# Hall_sensor_V1_power.net
KiCad netlist of a schematic drawn in Altium Designer
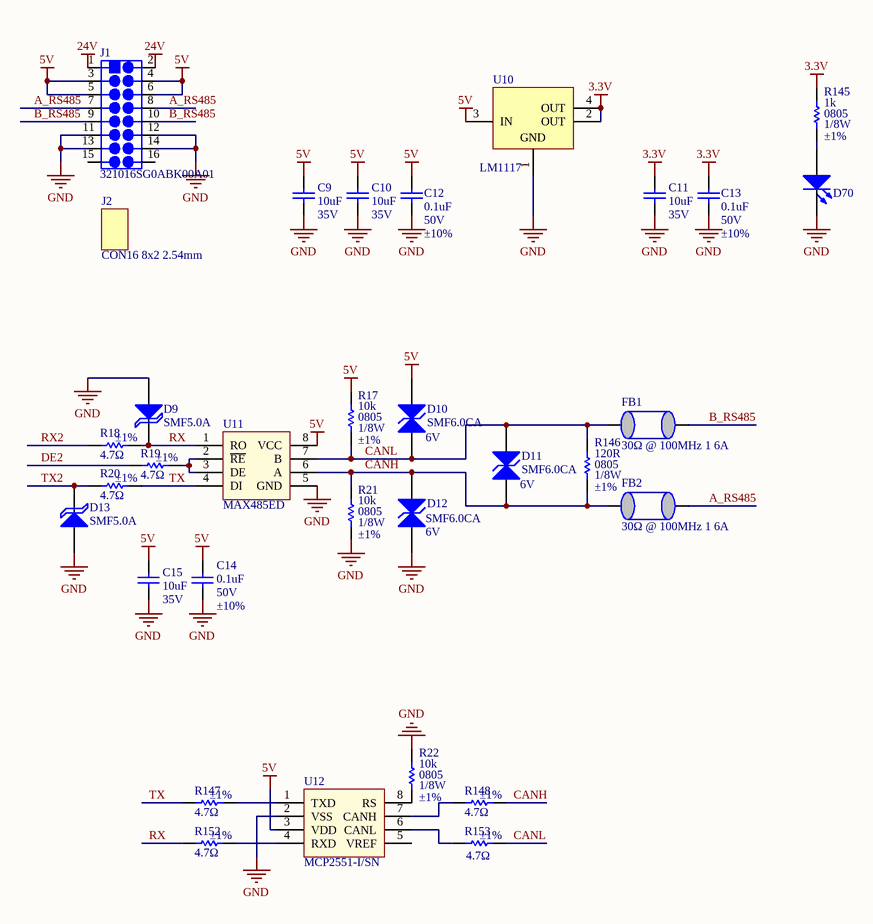
[diagram p0: Hall sensor V1 power.SchDoc]

(export (version "E")
  (design (tool "Eeschema 10.0.6"))
  (components
    (comp (ref "C9")
      (value "10uF")
      (footprint "CAP_SMD_0805")
      (description "10uF ±10% 35V X5R 0805 Multilayer Ceramic Capacitors MLCC - SMD/SMT RoHS")
      (fields
        (field (name "MANUFACTURER1_PART#") "GRM21BR6YA106KE43L")
        (field (name "MANUFACTURER2_PART#") "C2012X5R1V106MT000E")
        (field (name "VOLTAGE") "35V")
        (field (name "BY") "Thanh Son")
      )
      (libsource (lib "Full") (part "Cap-NP-100"))
    )
    (comp (ref "C10")
      (value "10uF")
      (footprint "CAP_SMD_0805")
      (description "10uF ±10% 35V X5R 0805 Multilayer Ceramic Capacitors MLCC - SMD/SMT RoHS")
      (fields
        (field (name "MANUFACTURER1_PART#") "GRM21BR6YA106KE43L")
        (field (name "MANUFACTURER2_PART#") "C2012X5R1V106MT000E")
        (field (name "VOLTAGE") "35V")
        (field (name "BY") "Thanh Son")
      )
      (libsource (lib "Full") (part "Cap-NP-100"))
    )
    (comp (ref "C11")
      (value "10uF")
      (footprint "CAP_SMD_0805")
      (description "10uF ±10% 35V X5R 0805 Multilayer Ceramic Capacitors MLCC - SMD/SMT RoHS")
      (fields
        (field (name "MANUFACTURER1_PART#") "GRM21BR6YA106KE43L")
        (field (name "MANUFACTURER2_PART#") "C2012X5R1V106MT000E")
        (field (name "VOLTAGE") "35V")
        (field (name "BY") "Thanh Son")
      )
      (libsource (lib "Full") (part "Cap-NP-100"))
    )
    (comp (ref "C12")
      (value "0.1uF")
      (footprint "CAP_SMD_0805")
      (description "100nF ±10% 50V X7R 0805 Multilayer Ceramic Capacitors MLCC - SMD/SMT RoHS")
      (fields
        (field (name "MANUFACTURER1_PART#") "C0805B104K500NT")
        (field (name "MANUFACTURER2_PART#") "TCC0805X7R104K500DT")
        (field (name "VOLTAGE") "50V")
        (field (name "TOLERANCE") "±10%")
        (field (name "BY") "Thanh Son")
      )
      (libsource (lib "Full") (part "Cap-NP-100"))
    )
    (comp (ref "C13")
      (value "0.1uF")
      (footprint "CAP_SMD_0805")
      (description "100nF ±10% 50V X7R 0805 Multilayer Ceramic Capacitors MLCC - SMD/SMT RoHS")
      (fields
        (field (name "MANUFACTURER1_PART#") "C0805B104K500NT")
        (field (name "MANUFACTURER2_PART#") "TCC0805X7R104K500DT")
        (field (name "VOLTAGE") "50V")
        (field (name "TOLERANCE") "±10%")
        (field (name "BY") "Thanh Son")
      )
      (libsource (lib "Full") (part "Cap-NP-100"))
    )
    (comp (ref "C14")
      (value "0.1uF")
      (footprint "CAP_SMD_0805")
      (description "100nF ±10% 50V X7R 0805 Multilayer Ceramic Capacitors MLCC - SMD/SMT RoHS")
      (fields
        (field (name "MANUFACTURER1_PART#") "C0805B104K500NT")
        (field (name "MANUFACTURER2_PART#") "TCC0805X7R104K500DT")
        (field (name "VOLTAGE") "50V")
        (field (name "TOLERANCE") "±10%")
        (field (name "BY") "Thanh Son")
      )
      (libsource (lib "Full") (part "Cap-NP-100"))
    )
    (comp (ref "C15")
      (value "10uF")
      (footprint "CAP_SMD_0805")
      (description "10uF ±10% 35V X5R 0805 Multilayer Ceramic Capacitors MLCC - SMD/SMT RoHS")
      (fields
        (field (name "MANUFACTURER1_PART#") "GRM21BR6YA106KE43L")
        (field (name "MANUFACTURER2_PART#") "C2012X5R1V106MT000E")
        (field (name "VOLTAGE") "35V")
        (field (name "BY") "Thanh Son")
      )
      (libsource (lib "Full") (part "Cap-NP-100"))
    )
    (comp (ref "D9")
      (value "SMF5.0A")
      (footprint "SOD-123")
      (description "SOD-123FL TVS RoHS")
      (fields (field (name "MANUFACTURER1_PART#") "SMF5.0A") (field (name "BY") "Thanh Son"))
      (libsource (lib "Full") (part "TVS SMF26A"))
    )
    (comp (ref "D10")
      (value "SMF6.0CA")
      (footprint "SOD-123")
      (description "Bidirectional 6V 6.67V 10.3V 19.4mA SOD-123FL TVS RoHS")
      (fields (field (name "VOLTAGE") "6V") (field (name "BY") "Thanh Son"))
      (libsource (lib "Full") (part "TVS SMF05CA  SOD123"))
    )
    (comp (ref "D11")
      (value "SMF6.0CA")
      (footprint "SOD-123")
      (description "Bidirectional 6V 6.67V 10.3V 19.4mA SOD-123FL TVS RoHS")
      (fields (field (name "VOLTAGE") "6V") (field (name "BY") "Thanh Son"))
      (libsource (lib "Full") (part "TVS SMF05CA  SOD123"))
    )
    (comp (ref "D12")
      (value "SMF6.0CA")
      (footprint "SOD-123")
      (description "Bidirectional 6V 6.67V 10.3V 19.4mA SOD-123FL TVS RoHS")
      (fields
        (field (name "MANUFACTURER1_PART#") "SMF6.0CA")
        (field (name "VOLTAGE") "6V")
        (field (name "BY") "Thanh Son")
      )
      (libsource (lib "Full") (part "TVS SMF05CA  SOD123"))
    )
    (comp (ref "D13")
      (value "SMF5.0A")
      (footprint "SOD-123")
      (description "SOD-123FL TVS RoHS")
      (fields (field (name "MANUFACTURER1_PART#") "SMF5.0A") (field (name "BY") "Thanh Son"))
      (libsource (lib "Full") (part "TVS SMF26A"))
    )
    (comp (ref "D70")
      (value "17-21/R6C-AQ2R2B/3T")
      (footprint "LED_SMD0805")
      (description "Red 617.5~633.5nm 0805 Light Emitting Diodes (LED) ROHS")
      (fields (field (name "MANUFACTURER2_PART#") "HSMH-C170"))
      (libsource (lib "Full") (part "LED_RED_SMD_0805"))
    )
    (comp (ref "FB1")
      (value "30Ω @ 100MHz 1 6A")
      (footprint "Inductor 0805")
      (description "30Ω @ 100MHz 1 6A 10mΩ 0805 Ferrite Beads ROHS")
      (fields
        (field (name "MANUFACTURER1_PART#") "CBM201209U300T")
        (field (name "MANUFACTURER2_PART#") "HCB2012KF-300T60")
        (field (name "BY") "Thanh Son")
      )
      (libsource (lib "Full") (part "inductor ferrite bead"))
    )
    (comp (ref "FB2")
      (value "30Ω @ 100MHz 1 6A")
      (footprint "Inductor 0805")
      (description "30Ω @ 100MHz 1 6A 10mΩ 0805 Ferrite Beads ROHS")
      (fields
        (field (name "MANUFACTURER1_PART#") "CBM201209U300T")
        (field (name "MANUFACTURER2_PART#") "HCB2012KF-300T60")
        (field (name "BY") "Thanh Son")
      )
      (libsource (lib "Full") (part "inductor ferrite bead"))
    )
    (comp (ref "J1")
      (value "header16 8x2 2.54mm")
      (footprint "Header IDC 8x2 2.54mm through hold")
      (description "16 2 0.100\"(2.54mm) Header Through Hole,P=2.54mm IDC Connectors ROHS")
      (fields
        (field (name "MANUFACTURER2_PART#") "B-3000S16P-0110")
        (field (name "MANUFACTURER1_PART#") "321016SG0ABK00A01")
        (field (name "BY") "Thanh Son")
      )
      (libsource (lib "Full") (part "header 8x2 JILN"))
    )
    (comp (ref "J2")
      (value "CON16 8x2 2.54mm")
      (description "16 2 0.100\"(2.54mm) - IDCconnector P=2.54mm IDC Connectors ROHS")
      (fields
        (field (name "MANUFACTURER1_PART#") "531416YBS0BW01")
        (field (name "MANUFACTURER2_PART#") "I-1010316P-B000")
        (field (name "BY") "Thanh Son")
      )
      (libsource (lib "Full") (part "CON 2 WJ2EDGR-5.08-2P"))
    )
    (comp (ref "R17")
      (value "10k")
      (footprint "RES_SMD_0805")
      (description "10kΩ ±1% 1/8W ±100ppm/℃ 0805 Chip Resistor - Surface Mount RoHS")
      (fields
        (field (name "MANUFACTURER1_PART#") "0805W8F1002T5E")
        (field (name "MANUFACTURER2_PART#") "RS-05K1002FT")
        (field (name "PCB FOOTPRINT") "0805")
        (field (name "POWER") "1/8W")
        (field (name "TOLERANCE") "±1%")
        (field (name "BY") "Thanh Son")
      )
      (libsource (lib "Full") (part "Res0.3"))
    )
    (comp (ref "R18")
      (value "4.7Ω")
      (footprint "RES_SMD_0805")
      (description "4.7Ω ±1% ±400ppm/℃ 0.125W 0805 Chip Resistor - Surface Mount ROHS")
      (fields
        (field (name "MANUFACTURER1_PART#") "0805W8F470KT5E")
        (field (name "MANUFACTURER2_PART#") "RC0805FR-074R7L")
        (field (name "TOLERANCE") "±1%")
      )
      (libsource (lib "Full") (part "Res0.3"))
    )
    (comp (ref "R19")
      (value "4.7Ω")
      (footprint "RES_SMD_0805")
      (description "4.7Ω ±1% ±400ppm/℃ 0.125W 0805 Chip Resistor - Surface Mount ROHS")
      (fields
        (field (name "MANUFACTURER1_PART#") "0805W8F470KT5E")
        (field (name "MANUFACTURER2_PART#") "RC0805FR-074R7L")
        (field (name "TOLERANCE") "±1%")
      )
      (libsource (lib "Full") (part "Res0.3"))
    )
    (comp (ref "R20")
      (value "4.7Ω")
      (footprint "RES_SMD_0805")
      (description "4.7Ω ±1% ±400ppm/℃ 0.125W 0805 Chip Resistor - Surface Mount ROHS")
      (fields
        (field (name "MANUFACTURER1_PART#") "0805W8F470KT5E")
        (field (name "MANUFACTURER2_PART#") "RC0805FR-074R7L")
        (field (name "TOLERANCE") "±1%")
      )
      (libsource (lib "Full") (part "Res0.3"))
    )
    (comp (ref "R21")
      (value "10k")
      (footprint "RES_SMD_0805")
      (description "10kΩ ±1% 1/8W ±100ppm/℃ 0805 Chip Resistor - Surface Mount RoHS")
      (fields
        (field (name "MANUFACTURER1_PART#") "0805W8F1002T5E")
        (field (name "MANUFACTURER2_PART#") "RS-05K1002FT")
        (field (name "PCB FOOTPRINT") "0805")
        (field (name "POWER") "1/8W")
        (field (name "TOLERANCE") "±1%")
        (field (name "BY") "Thanh Son")
      )
      (libsource (lib "Full") (part "Res0.3"))
    )
    (comp (ref "R22")
      (value "10k")
      (footprint "RES_SMD_0805")
      (description "10kΩ ±1% 1/8W ±100ppm/℃ 0805 Chip Resistor - Surface Mount RoHS")
      (fields
        (field (name "MANUFACTURER1_PART#") "0805W8F1002T5E")
        (field (name "MANUFACTURER2_PART#") "RS-05K1002FT")
        (field (name "PCB FOOTPRINT") "0805")
        (field (name "POWER") "1/8W")
        (field (name "TOLERANCE") "±1%")
        (field (name "BY") "Thanh Son")
      )
      (libsource (lib "Full") (part "Res0.3"))
    )
    (comp (ref "R145")
      (value "1k")
      (footprint "RES_SMD_0805")
      (description "10kΩ ±1% 1/8W ±100ppm/℃ 0805 Chip Resistor - Surface Mount RoHS")
      (fields
        (field (name "MANUFACTURER1_PART#") "AC0805FR-071KL")
        (field (name "MANUFACTURER2_PART#") "WR08X1001FTL")
        (field (name "PCB FOOTPRINT") "0805")
        (field (name "POWER") "1/8W")
        (field (name "TOLERANCE") "±1%")
        (field (name "BY") "Thanh Son")
      )
      (libsource (lib "Full") (part "Res0.3"))
    )
    (comp (ref "R146")
      (value "120R")
      (footprint "RES_SMD_0805")
      (description "±1% ±100ppm/℃ 120Ω 0.125W 0805 Chip Resistor - Surface Mount ROHS")
      (fields
        (field (name "MANUFACTURER1_PART#") "0805W8F1200T5E")
        (field (name "MANUFACTURER2_PART#") "AC0805FR-7W120RL")
        (field (name "PCB FOOTPRINT") "0805")
        (field (name "POWER") "1/8W")
        (field (name "TOLERANCE") "±1%")
        (field (name "BY") "Thanh Son")
      )
      (libsource (lib "Full") (part "Res0.3"))
    )
    (comp (ref "R147")
      (value "4.7Ω")
      (footprint "RES_SMD_0805")
      (description "4.7Ω ±1% ±400ppm/℃ 0.125W 0805 Chip Resistor - Surface Mount ROHS")
      (fields
        (field (name "MANUFACTURER1_PART#") "0805W8F470KT5E")
        (field (name "MANUFACTURER2_PART#") "RC0805FR-074R7L")
        (field (name "TOLERANCE") "±1%")
      )
      (libsource (lib "Full") (part "Res0.3"))
    )
    (comp (ref "R148")
      (value "4.7Ω")
      (footprint "RES_SMD_0805")
      (description "4.7Ω ±1% ±400ppm/℃ 0.125W 0805 Chip Resistor - Surface Mount ROHS")
      (fields
        (field (name "MANUFACTURER1_PART#") "0805W8F470KT5E")
        (field (name "MANUFACTURER2_PART#") "RC0805FR-074R7L")
        (field (name "TOLERANCE") "±1%")
      )
      (libsource (lib "Full") (part "Res0.3"))
    )
    (comp (ref "R152")
      (value "4.7Ω")
      (footprint "RES_SMD_0805")
      (description "4.7Ω ±1% ±400ppm/℃ 0.125W 0805 Chip Resistor - Surface Mount ROHS")
      (fields
        (field (name "MANUFACTURER1_PART#") "0805W8F470KT5E")
        (field (name "MANUFACTURER2_PART#") "RC0805FR-074R7L")
        (field (name "TOLERANCE") "±1%")
      )
      (libsource (lib "Full") (part "Res0.3"))
    )
    (comp (ref "R153")
      (value "4.7Ω")
      (footprint "RES_SMD_0805")
      (description "4.7Ω ±1% ±400ppm/℃ 0.125W 0805 Chip Resistor - Surface Mount ROHS")
      (fields
        (field (name "MANUFACTURER1_PART#") "0805W8F470KT5E")
        (field (name "MANUFACTURER2_PART#") "RC0805FR-074R7L")
        (field (name "TOLERANCE") "±1%")
      )
      (libsource (lib "Full") (part "Res0.3"))
    )
    (comp (ref "U10")
      (value "LM1117")
      (footprint "SOT223")
      (description "Fixed 18V 3.3V 1.4V @ 1A SOT-223 Dropout Regulators(LDO) RoHS")
      (fields
        (field (name "MANUFACTURER1_PART#") "AMS1117-3.3")
        (field (name "VOLTAGE") "3.3V")
        (field (name "BY") "Thanh Son")
      )
      (libsource (lib "Full") (part "LM1117"))
    )
    (comp (ref "U11")
      (value "MAX485ED")
      (footprint "SOIC8")
      (description "Transceiver RS485 1/1 200kbps SOIC-8_150mil RS-485/RS-422 ICs RoHS")
      (fields (field (name "MANUFACTURER2_PART#") "CBM485AS8") (field (name "BY") "Thanh Son"))
      (libsource (lib "Full") (part "RS 485 SIT3485ESA"))
    )
    (comp (ref "U12")
      (value "MCP2551-I/SN")
      (footprint "SOIC8")
      (description "Transceiver 1/1 CAN - SOIC-8_150mil CAN ICs ROHS")
      (fields (field (name "MANUFACTURER2_PART#") "PCA82C250T/YM,118") (field (name "BY") "Thanh Son"))
      (libsource (lib "Full") (part "CAN MCP2551-I/SN"))
    )
  )
  (nets
    (net (code "1") (name "/A_RS485") (class "Default")
      (node (ref "FB2") (pin "2") (pinfunction "2_2") (pintype "passive"))
      (node (ref "J1") (pin "7") (pinfunction "7_7") (pintype "passive"))
      (node (ref "J1") (pin "8") (pinfunction "8_8") (pintype "passive"))
    )
    (net (code "2") (name "/B_RS485") (class "Default")
      (node (ref "FB1") (pin "2") (pinfunction "2_2") (pintype "passive"))
      (node (ref "J1") (pin "10") (pinfunction "10_10") (pintype "passive"))
      (node (ref "J1") (pin "9") (pinfunction "9_9") (pintype "passive"))
    )
    (net (code "3") (name "/CANH") (class "Default")
      (node (ref "D11") (pin "2") (pinfunction "A_2") (pintype "passive"))
      (node (ref "D12") (pin "1") (pinfunction "K_1") (pintype "passive"))
      (node (ref "FB2") (pin "1") (pinfunction "1_1") (pintype "passive"))
      (node (ref "R146") (pin "1") (pinfunction "1_1") (pintype "passive"))
      (node (ref "R148") (pin "1") (pinfunction "1_1") (pintype "passive"))
      (node (ref "R21") (pin "2") (pinfunction "2_2") (pintype "passive"))
      (node (ref "U11") (pin "6") (pinfunction "A_6") (pintype "passive"))
    )
    (net (code "4") (name "/CANL") (class "Default")
      (node (ref "D10") (pin "2") (pinfunction "A_2") (pintype "passive"))
      (node (ref "D11") (pin "1") (pinfunction "K_1") (pintype "passive"))
      (node (ref "FB1") (pin "1") (pinfunction "1_1") (pintype "passive"))
      (node (ref "R146") (pin "2") (pinfunction "2_2") (pintype "passive"))
      (node (ref "R153") (pin "1") (pinfunction "1_1") (pintype "passive"))
      (node (ref "R17") (pin "1") (pinfunction "1_1") (pintype "passive"))
      (node (ref "U11") (pin "7") (pinfunction "B_7") (pintype "passive"))
    )
    (net (code "5") (name "/DE2") (class "Default")
      (node (ref "R19") (pin "2") (pinfunction "2_2") (pintype "passive"))
    )
    (net (code "6") (name "/RX") (class "Default")
      (node (ref "D9") (pin "1") (pinfunction "K_1") (pintype "passive"))
      (node (ref "R152") (pin "2") (pinfunction "2_2") (pintype "passive"))
      (node (ref "R18") (pin "1") (pinfunction "1_1") (pintype "passive"))
      (node (ref "U11") (pin "1") (pinfunction "RO_1") (pintype "passive"))
    )
    (net (code "7") (name "/RX2") (class "Default")
      (node (ref "R18") (pin "2") (pinfunction "2_2") (pintype "passive"))
    )
    (net (code "8") (name "/TX") (class "Default")
      (node (ref "R147") (pin "2") (pinfunction "2_2") (pintype "passive"))
      (node (ref "R20") (pin "1") (pinfunction "1_1") (pintype "passive"))
      (node (ref "U11") (pin "4") (pinfunction "DI_4") (pintype "passive"))
    )
    (net (code "9") (name "/TX2") (class "Default")
      (node (ref "D13") (pin "1") (pinfunction "K_1") (pintype "passive"))
      (node (ref "R20") (pin "2") (pinfunction "2_2") (pintype "passive"))
    )
    (net (code "10") (name "3.3V") (class "Default")
      (node (ref "C11") (pin "1") (pinfunction "1_1") (pintype "passive"))
      (node (ref "C13") (pin "2") (pinfunction "2_2") (pintype "passive"))
      (node (ref "R145") (pin "2") (pinfunction "2_2") (pintype "passive"))
      (node (ref "U10") (pin "2") (pinfunction "OUT_2") (pintype "power_in"))
      (node (ref "U10") (pin "4") (pinfunction "OUT_4") (pintype "passive"))
    )
    (net (code "11") (name "5V") (class "Default")
      (node (ref "C10") (pin "1") (pinfunction "1_1") (pintype "passive"))
      (node (ref "C12") (pin "2") (pinfunction "2_2") (pintype "passive"))
      (node (ref "C14") (pin "2") (pinfunction "2_2") (pintype "passive"))
      (node (ref "C15") (pin "1") (pinfunction "1_1") (pintype "passive"))
      (node (ref "C9") (pin "1") (pinfunction "1_1") (pintype "passive"))
      (node (ref "D10") (pin "1") (pinfunction "K_1") (pintype "passive"))
      (node (ref "J1") (pin "3") (pinfunction "3_3") (pintype "passive"))
      (node (ref "J1") (pin "4") (pinfunction "4_4") (pintype "passive"))
      (node (ref "J1") (pin "5") (pinfunction "5_5") (pintype "passive"))
      (node (ref "J1") (pin "6") (pinfunction "6_6") (pintype "passive"))
      (node (ref "R17") (pin "2") (pinfunction "2_2") (pintype "passive"))
      (node (ref "U10") (pin "3") (pinfunction "IN_3") (pintype "power_in"))
      (node (ref "U11") (pin "8") (pinfunction "VCC_8") (pintype "passive"))
      (node (ref "U12") (pin "3") (pinfunction "VDD_3") (pintype "passive"))
    )
    (net (code "12") (name "24V") (class "Default")
      (node (ref "J1") (pin "1") (pinfunction "1_1") (pintype "passive"))
      (node (ref "J1") (pin "2") (pinfunction "2_2") (pintype "passive"))
    )
    (net (code "13") (name "GND") (class "Default")
      (node (ref "C10") (pin "2") (pinfunction "2_2") (pintype "passive"))
      (node (ref "C11") (pin "2") (pinfunction "2_2") (pintype "passive"))
      (node (ref "C12") (pin "1") (pinfunction "1_1") (pintype "passive"))
      (node (ref "C13") (pin "1") (pinfunction "1_1") (pintype "passive"))
      (node (ref "C14") (pin "1") (pinfunction "1_1") (pintype "passive"))
      (node (ref "C15") (pin "2") (pinfunction "2_2") (pintype "passive"))
      (node (ref "C9") (pin "2") (pinfunction "2_2") (pintype "passive"))
      (node (ref "D12") (pin "2") (pinfunction "A_2") (pintype "passive"))
      (node (ref "D13") (pin "2") (pinfunction "A_2") (pintype "passive"))
      (node (ref "D70") (pin "1") (pinfunction "A_1") (pintype "passive"))
      (node (ref "D9") (pin "2") (pinfunction "A_2") (pintype "passive"))
      (node (ref "J1") (pin "11") (pinfunction "11_11") (pintype "passive"))
      (node (ref "J1") (pin "12") (pinfunction "12_12") (pintype "passive"))
      (node (ref "J1") (pin "13") (pinfunction "13_13") (pintype "passive"))
      (node (ref "J1") (pin "14") (pinfunction "14_14") (pintype "passive"))
      (node (ref "R21") (pin "1") (pinfunction "1_1") (pintype "passive"))
      (node (ref "R22") (pin "2") (pinfunction "2_2") (pintype "passive"))
      (node (ref "U10") (pin "1") (pinfunction "GND_1") (pintype "power_in"))
      (node (ref "U11") (pin "5") (pinfunction "GND_5") (pintype "passive"))
      (node (ref "U12") (pin "2") (pinfunction "VSS_2") (pintype "passive"))
    )
    (net (code "14") (name "Net-(D70-K)") (class "Default")
      (node (ref "D70") (pin "2") (pinfunction "K_2") (pintype "passive"))
      (node (ref "R145") (pin "1") (pinfunction "1_1") (pintype "passive"))
    )
    (net (code "15") (name "Net-(U11-DE)") (class "Default")
      (node (ref "R19") (pin "1") (pinfunction "1_1") (pintype "passive"))
      (node (ref "U11") (pin "2") (pinfunction "~{RE}_2") (pintype "passive"))
      (node (ref "U11") (pin "3") (pinfunction "DE_3") (pintype "passive"))
    )
    (net (code "16") (name "Net-(U12-CANH)") (class "Default")
      (node (ref "R148") (pin "2") (pinfunction "2_2") (pintype "passive"))
      (node (ref "U12") (pin "7") (pinfunction "CANH_7") (pintype "passive"))
    )
    (net (code "17") (name "Net-(U12-CANL)") (class "Default")
      (node (ref "R153") (pin "2") (pinfunction "2_2") (pintype "passive"))
      (node (ref "U12") (pin "6") (pinfunction "CANL_6") (pintype "passive"))
    )
    (net (code "18") (name "Net-(U12-RS)") (class "Default")
      (node (ref "R22") (pin "1") (pinfunction "1_1") (pintype "passive"))
      (node (ref "U12") (pin "8") (pinfunction "RS_8") (pintype "passive"))
    )
    (net (code "19") (name "Net-(U12-RXD)") (class "Default")
      (node (ref "R152") (pin "1") (pinfunction "1_1") (pintype "passive"))
      (node (ref "U12") (pin "4") (pinfunction "RXD_4") (pintype "passive"))
    )
    (net (code "20") (name "Net-(U12-TXD)") (class "Default")
      (node (ref "R147") (pin "1") (pinfunction "1_1") (pintype "passive"))
      (node (ref "U12") (pin "1") (pinfunction "TXD_1") (pintype "passive"))
    )
    (net (code "21") (name "unconnected-(J1-Pad15)") (class "Default")
      (node (ref "J1") (pin "15") (pinfunction "15_15") (pintype "passive"))
    )
    (net (code "22") (name "unconnected-(J1-Pad16)") (class "Default")
      (node (ref "J1") (pin "16") (pinfunction "16_16") (pintype "passive"))
    )
    (net (code "23") (name "unconnected-(J2-Pad1)") (class "Default")
      (node (ref "J2") (pin "1") (pintype "passive"))
    )
    (net (code "24") (name "unconnected-(J2-Pad2)") (class "Default")
      (node (ref "J2") (pin "2") (pintype "passive"))
    )
    (net (code "25") (name "unconnected-(U12-VREF-Pad5)") (class "Default")
      (node (ref "U12") (pin "5") (pinfunction "VREF_5") (pintype "passive"))
    )
  )
)
